# LightBox1_New.net
KiCad netlist of a schematic drawn in EAGLE
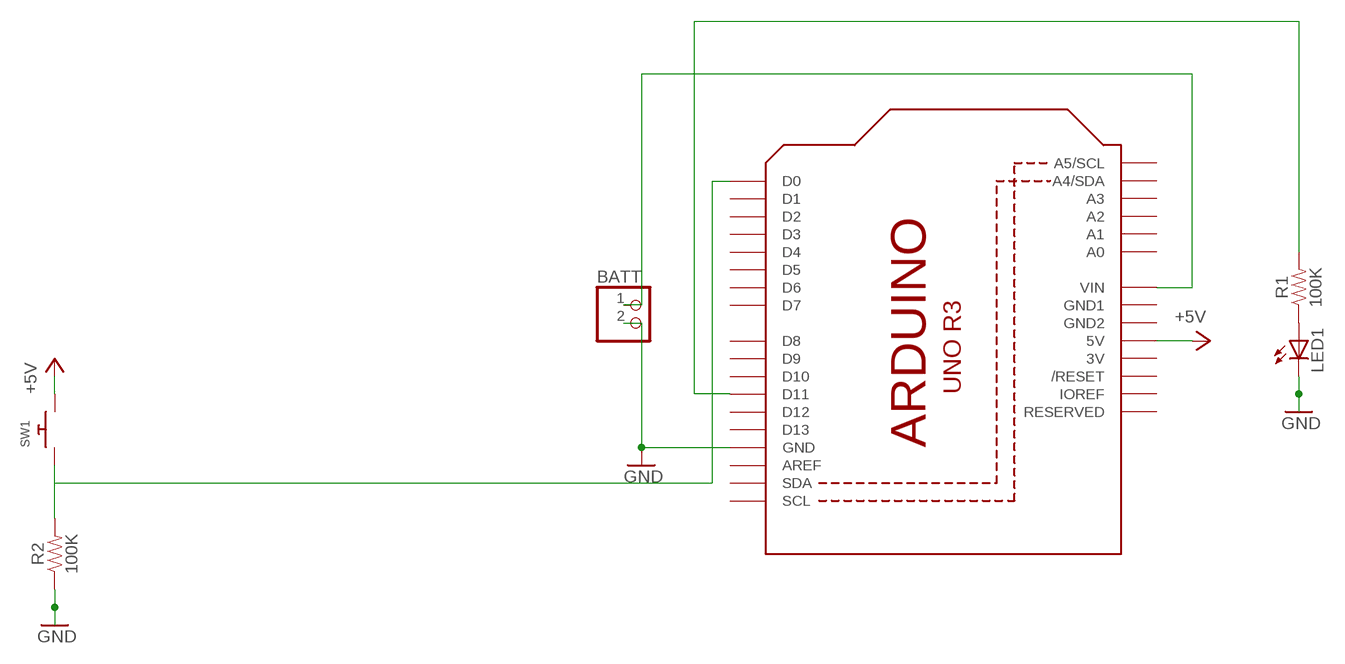
[diagram p0: schematic, sheet 1]

(export (version "E")
  (design (tool "Eeschema 10.0.6"))
  (components
    (comp (ref "BATT")
      (value "PINHD-1X2")
      (footprint "eagle-import:1X02")
      (libsource (lib "eagle-import") (part "PINHD-1X2"))
    )
    (comp (ref "LED1")
      (value "LED3MM")
      (footprint "eagle-import:LED3MM")
      (libsource (lib "eagle-import") (part "LED3MM"))
    )
    (comp (ref "R1")
      (value "100K")
      (footprint "eagle-import:0402")
      (libsource (lib "eagle-import") (part "100KOHM-0402-1/16W-1%"))
    )
    (comp (ref "R2")
      (value "100K")
      (footprint "eagle-import:0402")
      (libsource (lib "eagle-import") (part "100KOHM-0402-1/16W-1%"))
    )
    (comp (ref "SW1")
      (value "SWITCH_PUSHBUTTONSOFTTOUCHSMD_SJ")
      (footprint "eagle-import:PUSHBUTTON_SMD_SJ")
      (libsource (lib "eagle-import") (part "SWITCH_PUSHBUTTONSOFTTOUCHSMD_SJ"))
    )
    (comp (ref "U1")
      (value "ARDUINOR3-DIMENSION")
      (footprint "eagle-import:ARDUINOR3")
      (libsource (lib "eagle-import") (part "ARDUINOR3-DIMENSION"))
    )
  )
  (nets
    (net (code "1") (name "+5V") (class "Default")
      (node (ref "SW1") (pin "P$2") (pinfunction "P$2_P$2") (pintype "passive"))
      (node (ref "U1") (pin "5V") (pinfunction "5V_5V") (pintype "power_in"))
    )
    (net (code "2") (name "/3V") (class "Default")
      (node (ref "U1") (pin "3V") (pinfunction "3V_3V") (pintype "power_in"))
    )
    (net (code "3") (name "/GND1") (class "Default")
      (node (ref "U1") (pin "GND1") (pinfunction "GND1_GND1") (pintype "power_in"))
    )
    (net (code "4") (name "/GND2") (class "Default")
      (node (ref "U1") (pin "GND2") (pinfunction "GND2_GND2") (pintype "power_in"))
    )
    (net (code "5") (name "GND") (class "Default")
      (node (ref "BATT") (pin "2") (pinfunction "2_2") (pintype "passive"))
      (node (ref "LED1") (pin "K") (pinfunction "C_K") (pintype "passive"))
      (node (ref "R2") (pin "1") (pinfunction "1_1") (pintype "passive"))
      (node (ref "U1") (pin "GND") (pinfunction "GND_GND") (pintype "power_in"))
    )
    (net (code "6") (name "Net-(BATT-Pad1)") (class "Default")
      (node (ref "BATT") (pin "1") (pinfunction "1_1") (pintype "passive"))
      (node (ref "U1") (pin "VIN") (pinfunction "VIN_VIN") (pintype "power_in"))
    )
    (net (code "7") (name "Net-(LED1-PadA)") (class "Default")
      (node (ref "LED1") (pin "A") (pinfunction "A_A") (pintype "passive"))
      (node (ref "R1") (pin "1") (pinfunction "1_1") (pintype "passive"))
    )
    (net (code "8") (name "Net-(R1-Pad2)") (class "Default")
      (node (ref "R1") (pin "2") (pinfunction "2_2") (pintype "passive"))
      (node (ref "U1") (pin "D11") (pinfunction "D11_D11") (pintype "bidirectional"))
    )
    (net (code "9") (name "Net-(R2-Pad2)") (class "Default")
      (node (ref "R2") (pin "2") (pinfunction "2_2") (pintype "passive"))
      (node (ref "SW1") (pin "P$1") (pinfunction "P$1_P$1") (pintype "passive"))
      (node (ref "U1") (pin "D0") (pinfunction "D0_D0") (pintype "bidirectional"))
    )
    (net (code "10") (name "unconnected-(U1-A4{slash}SDA-PadA4)") (class "Default")
      (node (ref "U1") (pin "A4") (pinfunction "A4/SDA_A4") (pintype "bidirectional"))
    )
    (net (code "11") (name "unconnected-(U1-A5{slash}SCL-PadA5)") (class "Default")
      (node (ref "U1") (pin "A5") (pinfunction "A5/SCL_A5") (pintype "bidirectional"))
    )
    (net (code "12") (name "unconnected-(U1-PadA0)") (class "Default")
      (node (ref "U1") (pin "A0") (pinfunction "A0_A0") (pintype "bidirectional"))
    )
    (net (code "13") (name "unconnected-(U1-PadA1)") (class "Default")
      (node (ref "U1") (pin "A1") (pinfunction "A1_A1") (pintype "bidirectional"))
    )
    (net (code "14") (name "unconnected-(U1-PadA2)") (class "Default")
      (node (ref "U1") (pin "A2") (pinfunction "A2_A2") (pintype "bidirectional"))
    )
    (net (code "15") (name "unconnected-(U1-PadA3)") (class "Default")
      (node (ref "U1") (pin "A3") (pinfunction "A3_A3") (pintype "bidirectional"))
    )
    (net (code "16") (name "unconnected-(U1-PadAREF)") (class "Default")
      (node (ref "U1") (pin "AREF") (pinfunction "AREF_AREF") (pintype "bidirectional"))
    )
    (net (code "17") (name "unconnected-(U1-PadD1)") (class "Default")
      (node (ref "U1") (pin "D1") (pinfunction "D1_D1") (pintype "bidirectional"))
    )
    (net (code "18") (name "unconnected-(U1-PadD2)") (class "Default")
      (node (ref "U1") (pin "D2") (pinfunction "D2_D2") (pintype "bidirectional"))
    )
    (net (code "19") (name "unconnected-(U1-PadD3)") (class "Default")
      (node (ref "U1") (pin "D3") (pinfunction "D3_D3") (pintype "bidirectional"))
    )
    (net (code "20") (name "unconnected-(U1-PadD4)") (class "Default")
      (node (ref "U1") (pin "D4") (pinfunction "D4_D4") (pintype "bidirectional"))
    )
    (net (code "21") (name "unconnected-(U1-PadD5)") (class "Default")
      (node (ref "U1") (pin "D5") (pinfunction "D5_D5") (pintype "bidirectional"))
    )
    (net (code "22") (name "unconnected-(U1-PadD6)") (class "Default")
      (node (ref "U1") (pin "D6") (pinfunction "D6_D6") (pintype "bidirectional"))
    )
    (net (code "23") (name "unconnected-(U1-PadD7)") (class "Default")
      (node (ref "U1") (pin "D7") (pinfunction "D7_D7") (pintype "bidirectional"))
    )
    (net (code "24") (name "unconnected-(U1-PadD8)") (class "Default")
      (node (ref "U1") (pin "D8") (pinfunction "D8_D8") (pintype "bidirectional"))
    )
    (net (code "25") (name "unconnected-(U1-PadD9)") (class "Default")
      (node (ref "U1") (pin "D9") (pinfunction "D9_D9") (pintype "bidirectional"))
    )
    (net (code "26") (name "unconnected-(U1-PadD10)") (class "Default")
      (node (ref "U1") (pin "D10") (pinfunction "D10_D10") (pintype "bidirectional"))
    )
    (net (code "27") (name "unconnected-(U1-PadD12)") (class "Default")
      (node (ref "U1") (pin "D12") (pinfunction "D12_D12") (pintype "bidirectional"))
    )
    (net (code "28") (name "unconnected-(U1-PadD13)") (class "Default")
      (node (ref "U1") (pin "D13") (pinfunction "D13_D13") (pintype "bidirectional"))
    )
    (net (code "29") (name "unconnected-(U1-PadIOREF)") (class "Default")
      (node (ref "U1") (pin "IOREF") (pinfunction "IOREF_IOREF") (pintype "output"))
    )
    (net (code "30") (name "unconnected-(U1-PadRESERVED)") (class "Default")
      (node (ref "U1") (pin "RESERVED") (pinfunction "RESERVED_RESERVED") (pintype "no_connect"))
    )
    (net (code "31") (name "unconnected-(U1-PadSCL)") (class "Default")
      (node (ref "U1") (pin "SCL") (pinfunction "SCL_SCL") (pintype "bidirectional"))
    )
    (net (code "32") (name "unconnected-(U1-PadSDA)") (class "Default")
      (node (ref "U1") (pin "SDA") (pinfunction "SDA_SDA") (pintype "bidirectional"))
    )
    (net (code "33") (name "unconnected-(U1-{slash}RESET-PadRESET)") (class "Default")
      (node (ref "U1") (pin "RESET") (pinfunction "/RESET_RESET") (pintype "bidirectional"))
    )
  )
)
